# Main_7.net
KiCad netlist of a schematic drawn in Altium Designer
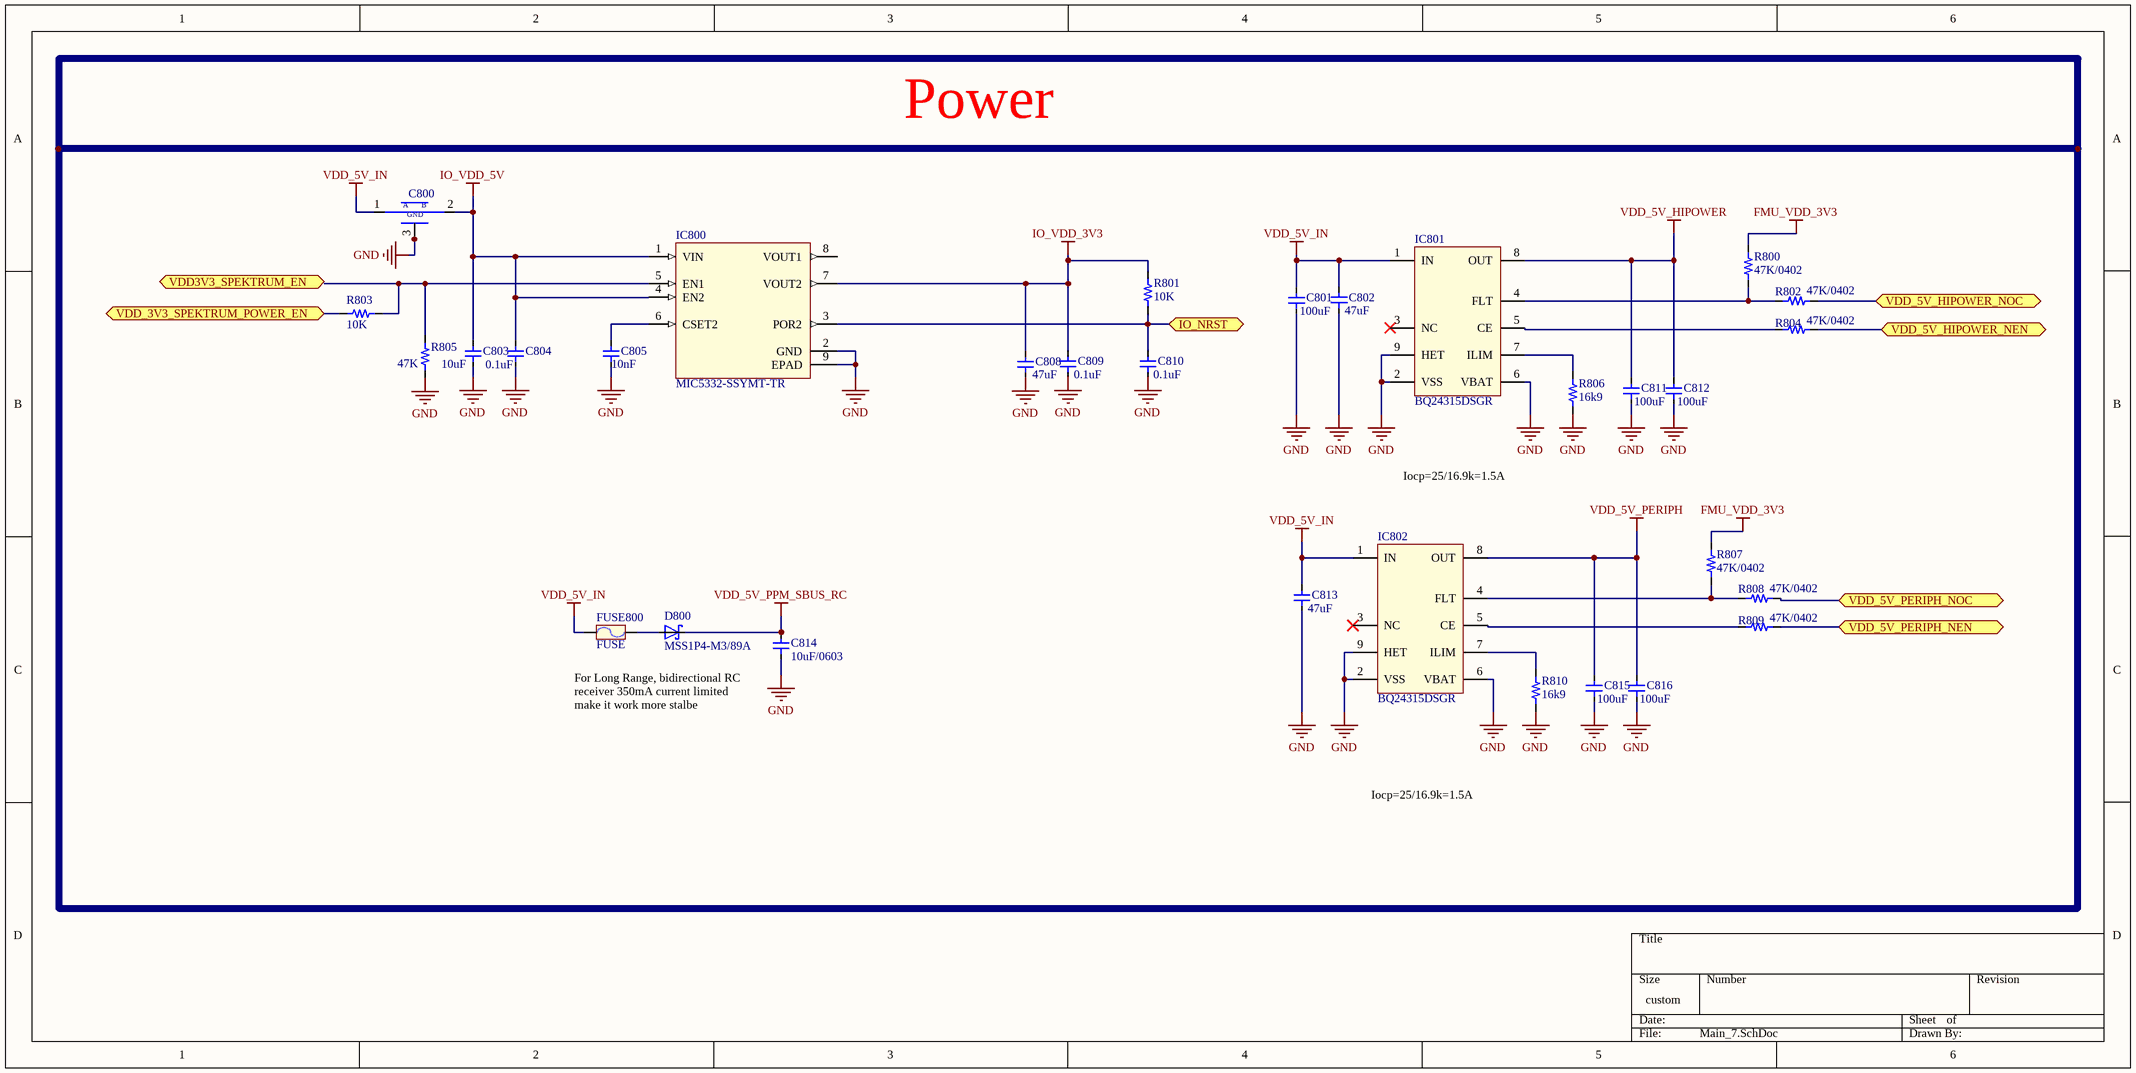
[diagram p0: Main_7.SchDoc]

(export (version "E")
  (design (tool "Eeschema 10.0.6"))
  (components
    (comp (ref "C800")
      (value "W2H13C1048AT1F")
      (footprint "W2H13C1048AT1F")
      (description "Feed Through Capacitors 25V 0.1uF X7R")
      (libsource (lib "UAV_mainboard") (part "W2H13C1048AT1F"))
    )
    (comp (ref "C801")
      (value "100uF")
      (footprint "C1206")
      (description "100 µF ±20% 6.3V Ceramic Capacitor X5R 1206 (3216 Metric)")
      (libsource (lib "UAV_mainboard") (part "CC1206MKX5R5BB107"))
    )
    (comp (ref "C802")
      (value "47uF")
      (footprint "C0805")
      (description "47 µF ±20% 10V Ceramic Capacitor X5R 0805 (2012 Metric)")
      (libsource (lib "UAV_mainboard") (part "GRM21BR61A476ME15L"))
    )
    (comp (ref "C803")
      (value "10uF")
      (footprint "C0603")
      (description "10 µF ±10% 10V Ceramic Capacitor X5R 0603 (1608 Metric)")
      (libsource (lib "UAV_mainboard") (part "CC0603KRX5R6BB106"))
    )
    (comp (ref "C804")
      (value "0.1uF")
      (footprint "C0603")
      (description "CAP CER 0.1UF 25V X7R 0603")
      (libsource (lib "UAV_mainboard") (part "CC0603KRX7R8BB104"))
    )
    (comp (ref "C805")
      (value "10nF")
      (footprint "C0603")
      (description "10000 pF ±5% 25V Ceramic Capacitor X7R 0603 (1608 Metric)")
      (libsource (lib "UAV_mainboard") (part "CC0603JRX7R8BB103"))
    )
    (comp (ref "C808")
      (value "47uF")
      (footprint "C0805")
      (description "47 µF ±20% 10V Ceramic Capacitor X5R 0805 (2012 Metric)")
      (libsource (lib "UAV_mainboard") (part "GRM21BR61A476ME15L"))
    )
    (comp (ref "C809")
      (value "0.1uF")
      (footprint "C0603")
      (description "CAP CER 0.1UF 25V X7R 0603")
      (libsource (lib "UAV_mainboard") (part "CC0603KRX7R8BB104"))
    )
    (comp (ref "C810")
      (value "0.1uF")
      (footprint "C0603")
      (description "CAP CER 0.1UF 25V X7R 0603")
      (libsource (lib "UAV_mainboard") (part "CC0603KRX7R8BB104"))
    )
    (comp (ref "C811")
      (value "100uF")
      (footprint "C1206")
      (description "100 µF ±20% 6.3V Ceramic Capacitor X5R 1206 (3216 Metric)")
      (libsource (lib "UAV_mainboard") (part "CC1206MKX5R5BB107"))
    )
    (comp (ref "C812")
      (value "100uF")
      (footprint "C1206")
      (description "100 µF ±20% 6.3V Ceramic Capacitor X5R 1206 (3216 Metric)")
      (libsource (lib "UAV_mainboard") (part "CC1206MKX5R5BB107"))
    )
    (comp (ref "C813")
      (value "47uF")
      (footprint "C0805")
      (description "47 µF ±20% 10V Ceramic Capacitor X5R 0805 (2012 Metric)")
      (libsource (lib "UAV_mainboard") (part "GRM21BR61A476ME15L"))
    )
    (comp (ref "C814")
      (value "10uF/0603")
      (footprint "C0603")
      (description "10 µF ±10% 10V Ceramic Capacitor X5R 0603 (1608 Metric)")
      (libsource (lib "UAV_mainboard") (part "CC0603KRX5R6BB106"))
    )
    (comp (ref "C815")
      (value "100uF")
      (footprint "C1206")
      (description "100 µF ±20% 6.3V Ceramic Capacitor X5R 1206 (3216 Metric)")
      (libsource (lib "UAV_mainboard") (part "CC1206MKX5R5BB107"))
    )
    (comp (ref "C816")
      (value "100uF")
      (footprint "C1206")
      (description "100 µF ±20% 6.3V Ceramic Capacitor X5R 1206 (3216 Metric)")
      (libsource (lib "UAV_mainboard") (part "CC1206MKX5R5BB107"))
    )
    (comp (ref "D800")
      (value "MSS1P4-M3/89A")
      (footprint "MSS1P4-M3/89A")
      (description "Diode 40 V 1A Surface Mount DO-219AD (MicroSMP)")
      (libsource (lib "UAV_mainboard") (part "MSS1P4-M3/89A"))
    )
    (comp (ref "FUSE800")
      (value "FUSE")
      (footprint "FUSE_1206")
      (description "Polymeric PTC Resettable Fuse 16V 350 mA Ih Surface Mount 1206 (3216 Metric), Concave")
      (libsource (lib "UAV_mainboard") (part "NANOSMDC035F-2"))
    )
    (comp (ref "IC800")
      (value "MIC5332-SSYMT-TR")
      (footprint "8-UFDFN")
      (libsource (lib "UAV_mainboard") (part "MIC5332-SSYMT-TR"))
    )
    (comp (ref "IC801")
      (value "BQ24315DSGR")
      (footprint "WSON-8")
      (description "Overvoltage & Overcurrent Protection IC & Li+ Charger Front-End Protection IC")
      (libsource (lib "UAV_mainboard") (part "BQ24315DSGR"))
    )
    (comp (ref "IC802")
      (value "BQ24315DSGR")
      (footprint "WSON-8")
      (description "Overvoltage & Overcurrent Protection IC & Li+ Charger Front-End Protection IC")
      (libsource (lib "UAV_mainboard") (part "BQ24315DSGR"))
    )
    (comp (ref "R800")
      (value "47K/0402")
      (footprint "R0402")
      (description "47 kOhms ±1% 0.063W, 1/16W Chip Resistor 0402 (1005 Metric) Moisture Resistant Thick Film")
      (libsource (lib "UAV_mainboard") (part "RC0402FR-0747KL"))
    )
    (comp (ref "R801")
      (value "10K")
      (footprint "R0402")
      (description "RES SMD 10K OHM 1% 1/16W 0402")
      (libsource (lib "UAV_mainboard") (part "RC1005F103CS"))
    )
    (comp (ref "R802")
      (value "47K/0402")
      (footprint "R0402")
      (description "47 kOhms ±1% 0.063W, 1/16W Chip Resistor 0402 (1005 Metric) Moisture Resistant Thick Film")
      (libsource (lib "UAV_mainboard") (part "RC0402FR-0747KL"))
    )
    (comp (ref "R803")
      (value "10K")
      (footprint "R0402")
      (description "RES SMD 10K OHM 1% 1/16W 0402")
      (libsource (lib "UAV_mainboard") (part "RC1005F103CS"))
    )
    (comp (ref "R804")
      (value "47K/0402")
      (footprint "R0402")
      (description "47 kOhms ±1% 0.063W, 1/16W Chip Resistor 0402 (1005 Metric) Moisture Resistant Thick Film")
      (libsource (lib "UAV_mainboard") (part "RC0402FR-0747KL"))
    )
    (comp (ref "R805")
      (value "47K")
      (footprint "R0402")
      (description "47 kOhms ±1% 0.063W, 1/16W Chip Resistor 0402 (1005 Metric) Moisture Resistant Thick Film")
      (libsource (lib "UAV_mainboard") (part "RC0402FR-0747KL"))
    )
    (comp (ref "R806")
      (value "16k9")
      (footprint "R0402")
      (description "16.9 kOhms ±1% 0.063W, 1/16W Chip Resistor 0402 (1005 Metric) Moisture Resistant Thick Film")
      (libsource (lib "UAV_mainboard") (part "RC0402FR-0716K9L"))
    )
    (comp (ref "R807")
      (value "47K/0402")
      (footprint "R0402")
      (description "47 kOhms ±1% 0.063W, 1/16W Chip Resistor 0402 (1005 Metric) Moisture Resistant Thick Film")
      (libsource (lib "UAV_mainboard") (part "RC0402FR-0747KL"))
    )
    (comp (ref "R808")
      (value "47K/0402")
      (footprint "R0402")
      (description "47 kOhms ±1% 0.063W, 1/16W Chip Resistor 0402 (1005 Metric) Moisture Resistant Thick Film")
      (libsource (lib "UAV_mainboard") (part "RC0402FR-0747KL"))
    )
    (comp (ref "R809")
      (value "47K/0402")
      (footprint "R0402")
      (description "47 kOhms ±1% 0.063W, 1/16W Chip Resistor 0402 (1005 Metric) Moisture Resistant Thick Film")
      (libsource (lib "UAV_mainboard") (part "RC0402FR-0747KL"))
    )
    (comp (ref "R810")
      (value "16k9")
      (footprint "R0402")
      (description "16.9 kOhms ±1% 0.063W, 1/16W Chip Resistor 0402 (1005 Metric) Moisture Resistant Thick Film")
      (libsource (lib "UAV_mainboard") (part "RC0402FR-0716K9L"))
    )
  )
  (nets
    (net (code "1") (name "/IO_NRST") (class "Default")
      (node (ref "C810") (pin "2") (pinfunction "2_2") (pintype "passive"))
      (node (ref "IC800") (pin "3") (pinfunction "POR2_3") (pintype "output"))
      (node (ref "R801") (pin "1") (pinfunction "1_1") (pintype "passive"))
    )
    (net (code "3") (name "/VDD_3V3_SPEKTRUM_POWER_EN") (class "Default")
      (node (ref "R803") (pin "1") (pinfunction "1_1") (pintype "passive"))
    )
    (net (code "4") (name "/VDD_5V_HIPOWER_NEN") (class "Default")
      (node (ref "R804") (pin "2") (pinfunction "2_2") (pintype "passive"))
    )
    (net (code "5") (name "/VDD_5V_HIPOWER_NOC") (class "Default")
      (node (ref "R802") (pin "2") (pinfunction "2_2") (pintype "passive"))
    )
    (net (code "6") (name "/VDD_5V_PERIPH_NEN") (class "Default")
      (node (ref "R809") (pin "2") (pinfunction "2_2") (pintype "passive"))
    )
    (net (code "7") (name "/VDD_5V_PERIPH_NOC") (class "Default")
      (node (ref "R808") (pin "2") (pinfunction "2_2") (pintype "passive"))
    )
    (net (code "8") (name "FMU_VDD_3V3") (class "Default")
      (node (ref "R800") (pin "1") (pinfunction "1_1") (pintype "passive"))
      (node (ref "R807") (pin "1") (pinfunction "1_1") (pintype "passive"))
    )
    (net (code "9") (name "GND") (class "Default")
      (node (ref "C800") (pin "3") (pintype "passive"))
      (node (ref "C800") (pin "4") (pinfunction "4_4") (pintype "passive"))
      (node (ref "C801") (pin "1") (pinfunction "1_1") (pintype "passive"))
      (node (ref "C802") (pin "1") (pinfunction "1_1") (pintype "passive"))
      (node (ref "C803") (pin "1") (pinfunction "1_1") (pintype "passive"))
      (node (ref "C804") (pin "1") (pinfunction "1_1") (pintype "passive"))
      (node (ref "C805") (pin "1") (pinfunction "1_1") (pintype "passive"))
      (node (ref "C808") (pin "1") (pinfunction "1_1") (pintype "passive"))
      (node (ref "C809") (pin "1") (pinfunction "1_1") (pintype "passive"))
      (node (ref "C810") (pin "1") (pinfunction "1_1") (pintype "passive"))
      (node (ref "C811") (pin "1") (pinfunction "1_1") (pintype "passive"))
      (node (ref "C812") (pin "1") (pinfunction "1_1") (pintype "passive"))
      (node (ref "C813") (pin "1") (pinfunction "1_1") (pintype "passive"))
      (node (ref "C814") (pin "1") (pinfunction "1_1") (pintype "passive"))
      (node (ref "C815") (pin "1") (pinfunction "1_1") (pintype "passive"))
      (node (ref "C816") (pin "1") (pinfunction "1_1") (pintype "passive"))
      (node (ref "IC800") (pin "2") (pinfunction "GND_2") (pintype "power_in"))
      (node (ref "IC800") (pin "9") (pinfunction "EPAD_9") (pintype "power_in"))
      (node (ref "IC801") (pin "2") (pinfunction "VSS_2") (pintype "passive"))
      (node (ref "IC801") (pin "6") (pinfunction "VBAT_6") (pintype "passive"))
      (node (ref "IC801") (pin "9") (pinfunction "HET_9") (pintype "passive"))
      (node (ref "IC802") (pin "2") (pinfunction "VSS_2") (pintype "passive"))
      (node (ref "IC802") (pin "6") (pinfunction "VBAT_6") (pintype "passive"))
      (node (ref "IC802") (pin "9") (pinfunction "HET_9") (pintype "passive"))
      (node (ref "R805") (pin "1") (pinfunction "1_1") (pintype "passive"))
      (node (ref "R806") (pin "1") (pinfunction "1_1") (pintype "passive"))
      (node (ref "R810") (pin "1") (pinfunction "1_1") (pintype "passive"))
    )
    (net (code "10") (name "IO_VDD_3V3") (class "Default")
      (node (ref "C808") (pin "2") (pinfunction "2_2") (pintype "passive"))
      (node (ref "C809") (pin "2") (pinfunction "2_2") (pintype "passive"))
      (node (ref "IC800") (pin "7") (pinfunction "VOUT2_7") (pintype "output"))
      (node (ref "R801") (pin "2") (pinfunction "2_2") (pintype "passive"))
    )
    (net (code "11") (name "IO_VDD_5V") (class "Default")
      (node (ref "C800") (pin "2") (pintype "passive"))
      (node (ref "C803") (pin "2") (pinfunction "2_2") (pintype "passive"))
      (node (ref "C804") (pin "2") (pinfunction "2_2") (pintype "passive"))
      (node (ref "IC800") (pin "1") (pinfunction "VIN_1") (pintype "input"))
      (node (ref "IC800") (pin "4") (pinfunction "EN2_4") (pintype "input"))
    )
    (net (code "12") (name "Net-(D800-A)") (class "Default")
      (node (ref "D800") (pin "2") (pinfunction "A_2") (pintype "passive"))
      (node (ref "FUSE800") (pin "2") (pinfunction "2_2") (pintype "passive"))
    )
    (net (code "13") (name "Net-(IC800-CSET2)") (class "Default")
      (node (ref "C805") (pin "2") (pinfunction "2_2") (pintype "passive"))
      (node (ref "IC800") (pin "6") (pinfunction "CSET2_6") (pintype "input"))
    )
    (net (code "14") (name "Net-(IC800-EN1)") (class "Default")
      (node (ref "IC800") (pin "5") (pinfunction "EN1_5") (pintype "input"))
      (node (ref "R803") (pin "2") (pinfunction "2_2") (pintype "passive"))
      (node (ref "R805") (pin "2") (pinfunction "2_2") (pintype "passive"))
    )
    (net (code "15") (name "Net-(IC801-CE)") (class "Default")
      (node (ref "IC801") (pin "5") (pinfunction "CE_5") (pintype "passive"))
      (node (ref "R804") (pin "1") (pinfunction "1_1") (pintype "passive"))
    )
    (net (code "16") (name "Net-(IC801-FLT)") (class "Default")
      (node (ref "IC801") (pin "4") (pinfunction "FLT_4") (pintype "passive"))
      (node (ref "R800") (pin "2") (pinfunction "2_2") (pintype "passive"))
      (node (ref "R802") (pin "1") (pinfunction "1_1") (pintype "passive"))
    )
    (net (code "17") (name "Net-(IC801-ILIM)") (class "Default")
      (node (ref "IC801") (pin "7") (pinfunction "ILIM_7") (pintype "passive"))
      (node (ref "R806") (pin "2") (pinfunction "2_2") (pintype "passive"))
    )
    (net (code "18") (name "Net-(IC802-CE)") (class "Default")
      (node (ref "IC802") (pin "5") (pinfunction "CE_5") (pintype "passive"))
      (node (ref "R809") (pin "1") (pinfunction "1_1") (pintype "passive"))
    )
    (net (code "19") (name "Net-(IC802-FLT)") (class "Default")
      (node (ref "IC802") (pin "4") (pinfunction "FLT_4") (pintype "passive"))
      (node (ref "R807") (pin "2") (pinfunction "2_2") (pintype "passive"))
      (node (ref "R808") (pin "1") (pinfunction "1_1") (pintype "passive"))
    )
    (net (code "20") (name "Net-(IC802-ILIM)") (class "Default")
      (node (ref "IC802") (pin "7") (pinfunction "ILIM_7") (pintype "passive"))
      (node (ref "R810") (pin "2") (pinfunction "2_2") (pintype "passive"))
    )
    (net (code "21") (name "VDD_5V_HIPOWER") (class "Default")
      (node (ref "C811") (pin "2") (pinfunction "2_2") (pintype "passive"))
      (node (ref "C812") (pin "2") (pinfunction "2_2") (pintype "passive"))
      (node (ref "IC801") (pin "8") (pinfunction "OUT_8") (pintype "passive"))
    )
    (net (code "22") (name "VDD_5V_IN") (class "Default")
      (node (ref "C800") (pin "1") (pintype "passive"))
      (node (ref "C801") (pin "2") (pinfunction "2_2") (pintype "passive"))
      (node (ref "C802") (pin "2") (pinfunction "2_2") (pintype "passive"))
      (node (ref "C813") (pin "2") (pinfunction "2_2") (pintype "passive"))
      (node (ref "FUSE800") (pin "1") (pinfunction "1_1") (pintype "passive"))
      (node (ref "IC801") (pin "1") (pinfunction "IN_1") (pintype "passive"))
      (node (ref "IC802") (pin "1") (pinfunction "IN_1") (pintype "passive"))
    )
    (net (code "23") (name "VDD_5V_PERIPH") (class "Default")
      (node (ref "C815") (pin "2") (pinfunction "2_2") (pintype "passive"))
      (node (ref "C816") (pin "2") (pinfunction "2_2") (pintype "passive"))
      (node (ref "IC802") (pin "8") (pinfunction "OUT_8") (pintype "passive"))
    )
    (net (code "24") (name "VDD_5V_PPM_SBUS_RC") (class "Default")
      (node (ref "C814") (pin "2") (pinfunction "2_2") (pintype "passive"))
      (node (ref "D800") (pin "1") (pinfunction "C_1") (pintype "passive"))
    )
    (net (code "25") (name "unconnected-(IC800-VOUT1-Pad8)") (class "Default")
      (node (ref "IC800") (pin "8") (pinfunction "VOUT1_8") (pintype "output"))
    )
    (net (code "26") (name "unconnected-(IC801-NC-Pad3)") (class "Default")
      (node (ref "IC801") (pin "3") (pinfunction "NC_3") (pintype "passive+no_connect"))
    )
    (net (code "27") (name "unconnected-(IC802-NC-Pad3)") (class "Default")
      (node (ref "IC802") (pin "3") (pinfunction "NC_3") (pintype "passive+no_connect"))
    )
  )
)
